# Push_Button.net
KiCad netlist of a schematic drawn in Altium Designer
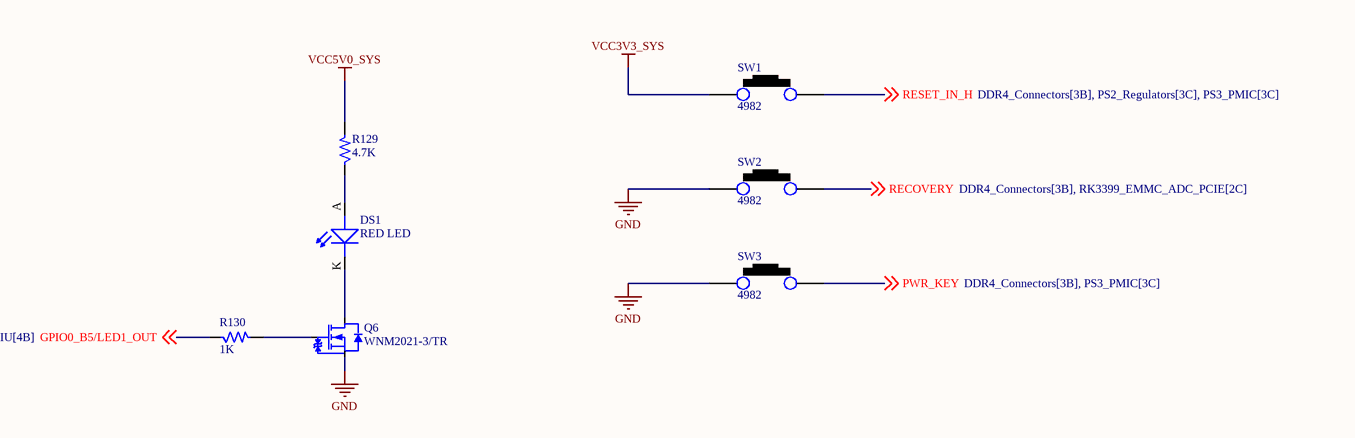
[diagram p0: Push_Button.SchDoc]

(export (version "E")
  (design (tool "Eeschema 10.0.6"))
  (components
    (comp (ref "DS1")
      (value "RED LED")
      (footprint "LED_0805")
      (description "Red 631nm LED Indication - Discrete 2V 0805 (2012 Metric)")
      (fields
        (field (name "MANUFACTURER") "Vishay Lite-On")
        (field (name "MANUFACTURER PART NUMBER") "LTST-C171KRKT")
      )
      (libsource (lib "EsteemPCB_SOM_Course_schlib") (part "LED_RED-2V-20mA-0805"))
    )
    (comp (ref "Q6")
      (value "WNM2021-3/TR")
      (footprint "SOT-323-3")
      (description "N Channel 20V 820mA 850mV @ 250uA 310mΩ @ 550mA,4.5V 310mW SOT-323(SC-70) MOSFET RoHS")
      (fields (field (name "MANUFACTURER") "WILLSEMI(Will Semicon)"))
      (libsource (lib "EsteemPCB_SOM_Course_schlib") (part "MOSFET-N_20V-820mA-SOT-323"))
    )
    (comp (ref "R129")
      (value "4.7K")
      (footprint "RES_0402")
      (description "4.7 kOhms ±1% 0.1W, 1/10W Chip Resistor 0402 (1005 Metric) Automotive AEC-Q200 Thick Film")
      (fields
        (field (name "MANUFACTURER") "Panasonic Electronic Components")
        (field (name "MANUFACTURER PART NUMBER") "ERJ-2RKF4701X")
      )
      (libsource (lib "EsteemPCB_SOM_Course_schlib") (part "RES_4.7K-0.1W-1%-0402"))
    )
    (comp (ref "R130")
      (value "1K")
      (footprint "RES_0402")
      (description "1 kOhms ±1% 0.1W, 1/10W Chip Resistor 0402 (1005 Metric) Anti-Sulfur Thin Film")
      (fields
        (field (name "MANUFACTURER") "Vishay Beyschlag/Draloric/BC Components")
        (field (name "MANUFACTURER PART NUMBER") "MCS04020C1001FE000")
      )
      (libsource (lib "EsteemPCB_SOM_Course_schlib") (part "RES_1K-0.1W-1%-0402"))
    )
    (comp (ref "SW1")
      (value "4982")
      (footprint "SW_177_39.3X77.7_SMD")
      (description "Tactile Switch 3x4x2mm SMD 2-Pin")
      (fields (field (name "MANUFACTURER") "NA"))
      (libsource (lib "EsteemPCB_SOM_Course_schlib") (part "SW1_4982"))
    )
    (comp (ref "SW2")
      (value "4982")
      (footprint "SW_177_39.3X77.7_SMD")
      (description "Tactile Switch 3x4x2mm SMD 2-Pin")
      (fields (field (name "MANUFACTURER") "NA"))
      (libsource (lib "EsteemPCB_SOM_Course_schlib") (part "SW1_4982"))
    )
    (comp (ref "SW3")
      (value "4982")
      (footprint "SW_177_39.3X77.7_SMD")
      (description "Tactile Switch 3x4x2mm SMD 2-Pin")
      (fields (field (name "MANUFACTURER") "NA"))
      (libsource (lib "EsteemPCB_SOM_Course_schlib") (part "SW1_4982"))
    )
  )
  (nets
    (net (code "1") (name "GND") (class "Default")
      (node (ref "Q6") (pin "2") (pinfunction "S_2") (pintype "passive"))
      (node (ref "SW2") (pin "1") (pinfunction "1_1") (pintype "passive"))
      (node (ref "SW3") (pin "1") (pinfunction "1_1") (pintype "passive"))
    )
    (net (code "2") (name "GPIO0_B5{slash}LED1_OUT") (class "Default")
      (node (ref "R130") (pin "1") (pinfunction "1_1") (pintype "passive"))
    )
    (net (code "3") (name "Net-(DS1-ANODE)") (class "Default")
      (node (ref "DS1") (pin "A") (pinfunction "ANODE_A") (pintype "passive"))
      (node (ref "R129") (pin "1") (pinfunction "1_1") (pintype "passive"))
    )
    (net (code "4") (name "Net-(DS1-CATHODE)") (class "Default")
      (node (ref "DS1") (pin "K") (pinfunction "CATHODE_K") (pintype "passive"))
      (node (ref "Q6") (pin "3") (pinfunction "D_3") (pintype "passive"))
    )
    (net (code "5") (name "Net-(Q6-G)") (class "Default")
      (node (ref "Q6") (pin "1") (pinfunction "G_1") (pintype "passive"))
      (node (ref "R130") (pin "2") (pinfunction "2_2") (pintype "passive"))
    )
    (net (code "6") (name "PWR_KEY") (class "Default")
      (node (ref "SW3") (pin "2") (pinfunction "2_2") (pintype "passive"))
    )
    (net (code "7") (name "RECOVERY") (class "Default")
      (node (ref "SW2") (pin "2") (pinfunction "2_2") (pintype "passive"))
    )
    (net (code "8") (name "RESET_IN_H") (class "Default")
      (node (ref "SW1") (pin "2") (pinfunction "2_2") (pintype "passive"))
    )
    (net (code "9") (name "VCC3V3_SYS") (class "Default")
      (node (ref "SW1") (pin "1") (pinfunction "1_1") (pintype "passive"))
    )
    (net (code "10") (name "VCC5V0_SYS") (class "Default")
      (node (ref "R129") (pin "2") (pinfunction "2_2") (pintype "passive"))
    )
  )
)
